# EEZ_tester_r1B2.net
KiCad netlist of a schematic drawn in EAGLE
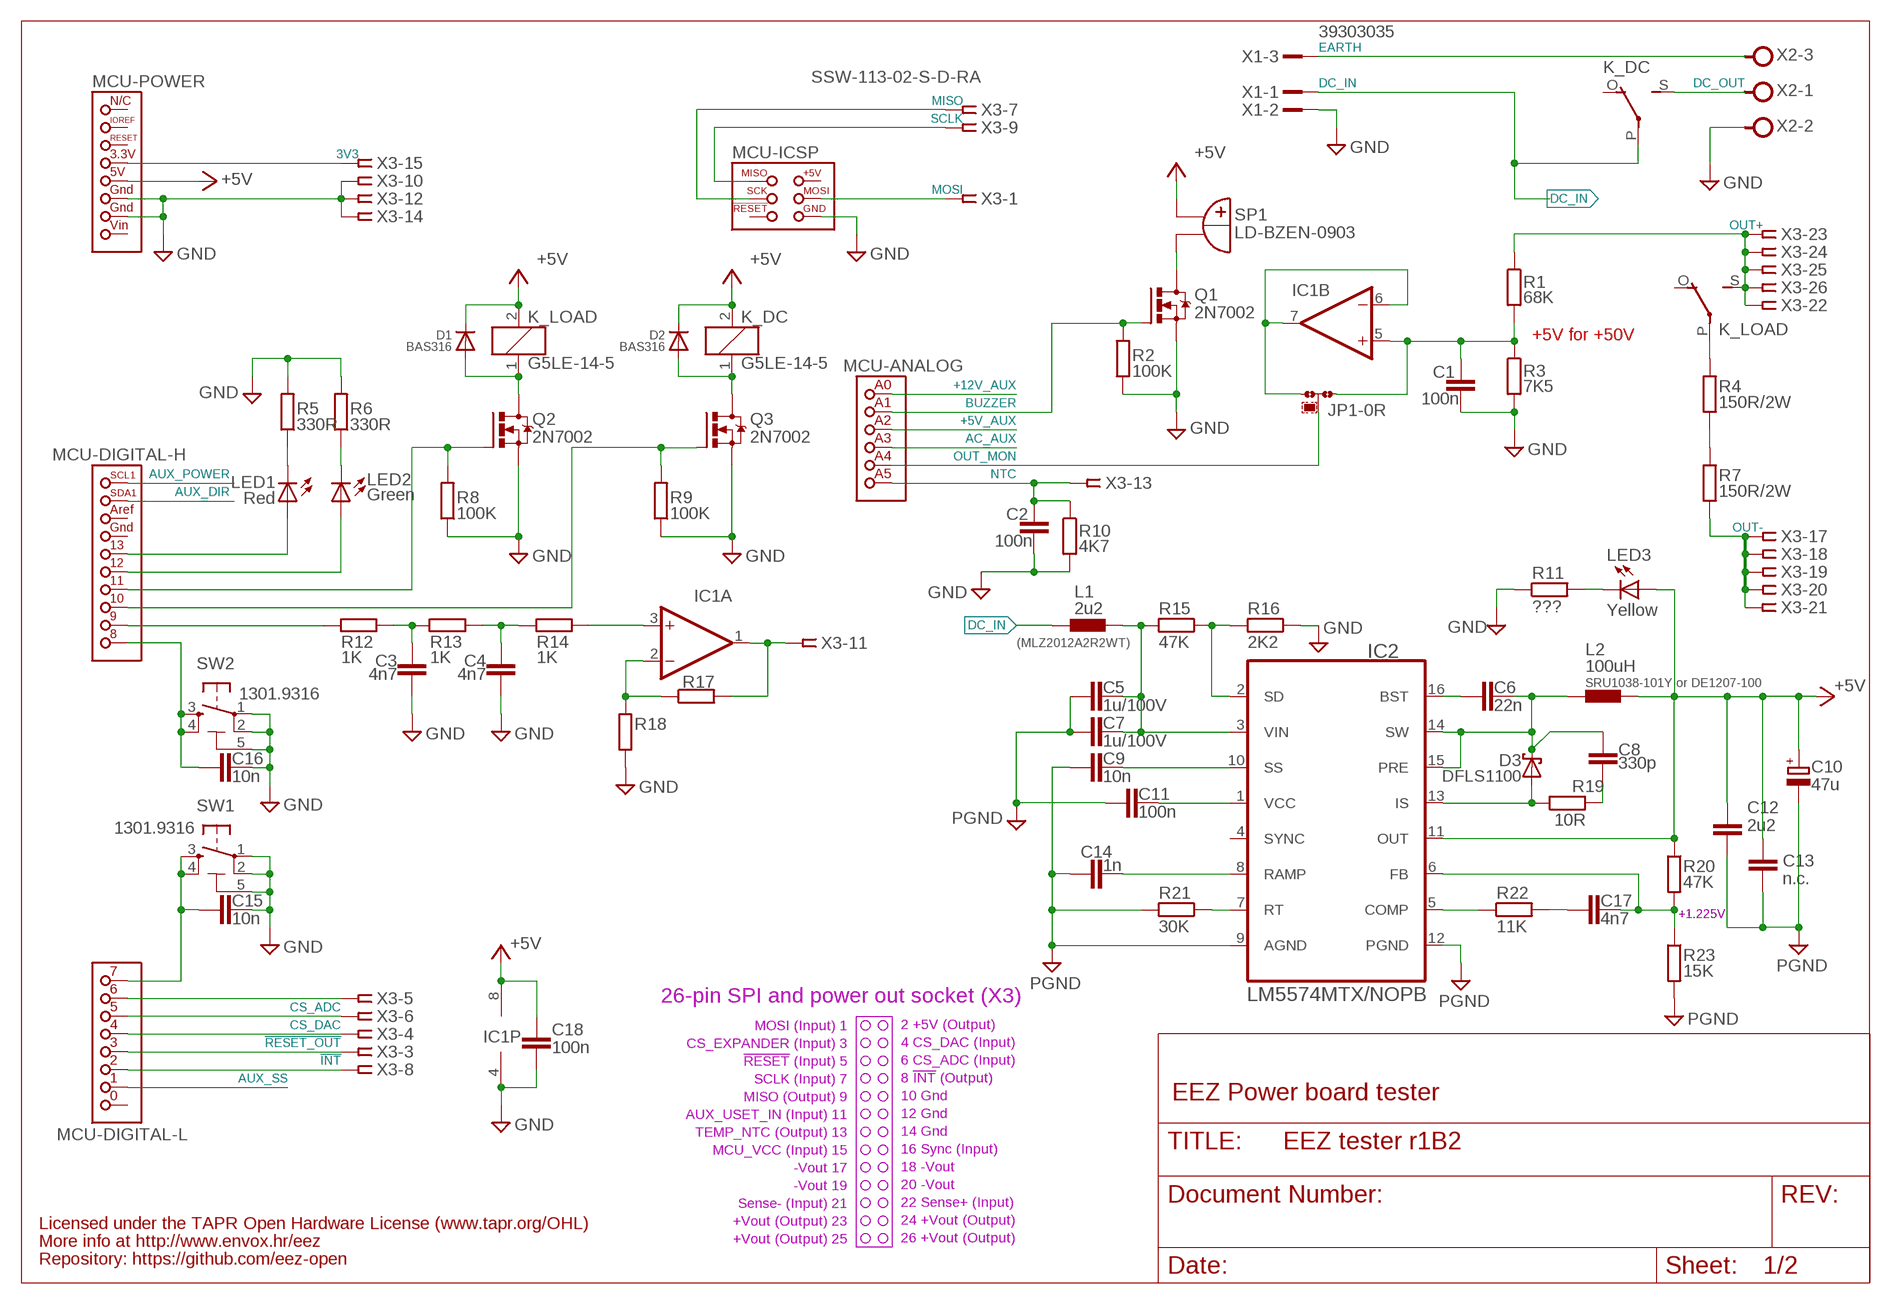
[diagram p0: schematic, sheet 1]
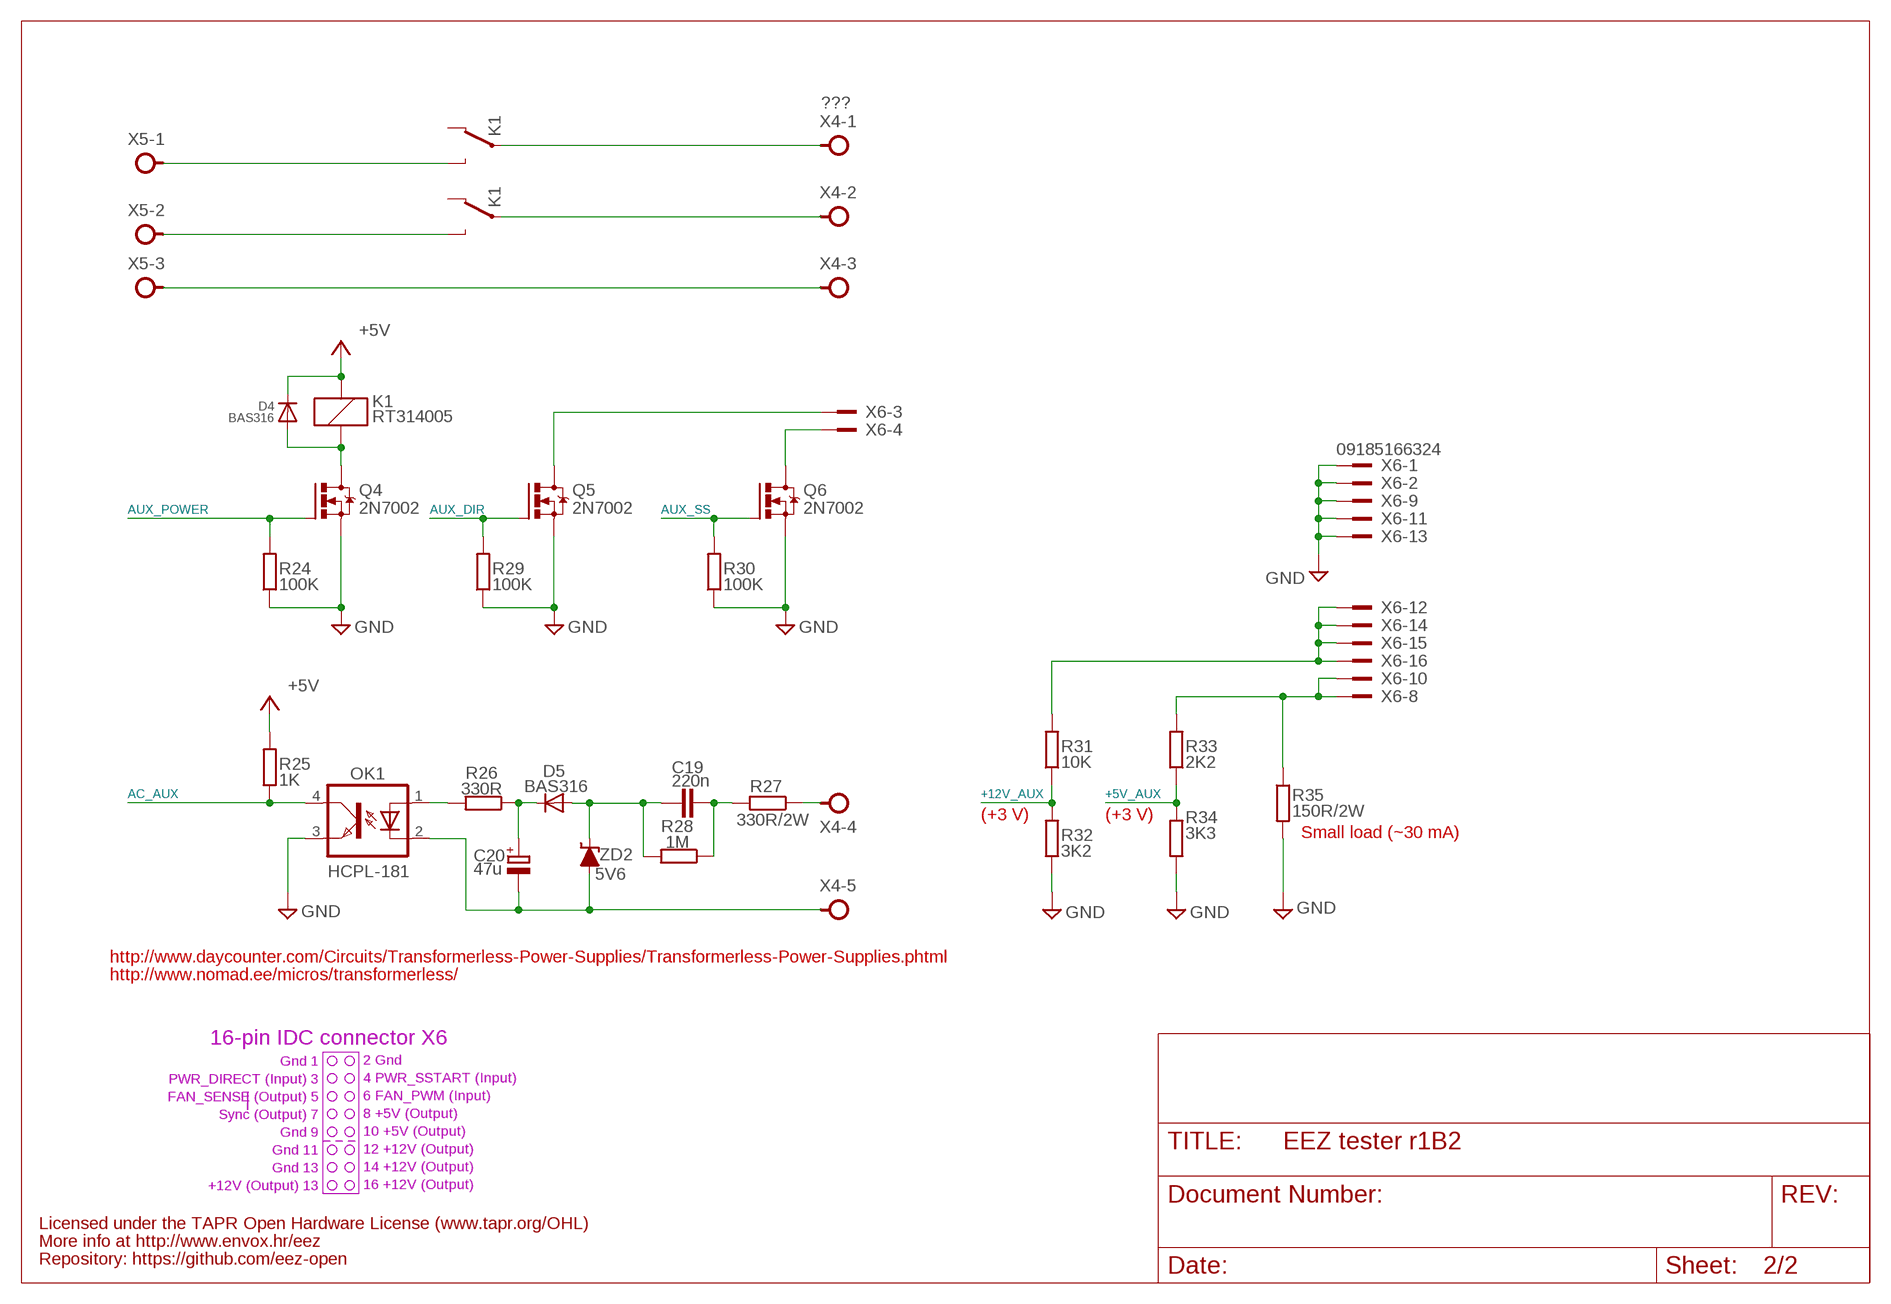
[diagram p1: schematic, sheet 2]

(export (version "E")
  (design (tool "Eeschema 10.0.6"))
  (components
    (comp (ref "C19")
      (value "220n")
      (footprint "eagle-import:C150-084X183")
      (libsource (lib "eagle-import") (part "C-EU150-084X183"))
    )
    (comp (ref "C20")
      (value "47u")
      (footprint "eagle-import:CAPAE660X610N")
      (libsource (lib "eagle-import") (part "ECAPPANASONIC_H"))
    )
    (comp (ref "D4")
      (value "BAS316")
      (footprint "eagle-import:SOD323-W")
      (libsource (lib "eagle-import") (part "DIODE-SOD323-W"))
    )
    (comp (ref "D5")
      (value "BAS316")
      (footprint "eagle-import:SOD323-W")
      (libsource (lib "eagle-import") (part "DIODE-SOD323-W"))
    )
    (comp (ref "K1")
      (value "RT314005")
      (footprint "eagle-import:RT-C_016A5_ROUND")
      (libsource (lib "eagle-import") (part "RELAY_RT314012-2"))
    )
    (comp (ref "OK1")
      (value "HCPL-181")
      (footprint "eagle-import:HCPL-181")
      (libsource (lib "eagle-import") (part "HCPL-181"))
    )
    (comp (ref "Q4")
      (value "2N7002")
      (footprint "eagle-import:SOT103P240X110-3N")
      (fields
        (field (name "MPN") "2N7002-7-F")
        (field (name "MPN_1") "2N7002-7-F")
        (field (name "OC_FARNELL") "1713823")
        (field (name "OC_NEWARK") "25R5679")
        (field (name "PACKAGE") "SOT-23-3")
        (field (name "SUPPLIER") "DIODES INC.")
      )
      (libsource (lib "eagle-import") (part "2N7002"))
    )
    (comp (ref "Q5")
      (value "2N7002")
      (footprint "eagle-import:SOT103P240X110-3N")
      (fields
        (field (name "MPN") "2N7002-7-F")
        (field (name "MPN_1") "2N7002-7-F")
        (field (name "OC_FARNELL") "1713823")
        (field (name "OC_NEWARK") "25R5679")
        (field (name "PACKAGE") "SOT-23-3")
        (field (name "SUPPLIER") "DIODES INC.")
      )
      (libsource (lib "eagle-import") (part "2N7002"))
    )
    (comp (ref "Q6")
      (value "2N7002")
      (footprint "eagle-import:SOT103P240X110-3N")
      (fields
        (field (name "MPN") "2N7002-7-F")
        (field (name "MPN_1") "2N7002-7-F")
        (field (name "OC_FARNELL") "1713823")
        (field (name "OC_NEWARK") "25R5679")
        (field (name "PACKAGE") "SOT-23-3")
        (field (name "SUPPLIER") "DIODES INC.")
      )
      (libsource (lib "eagle-import") (part "2N7002"))
    )
    (comp (ref "R24")
      (value "100K")
      (footprint "eagle-import:R0805")
      (libsource (lib "eagle-import") (part "R-EU_R0805"))
    )
    (comp (ref "R25")
      (value "1K")
      (footprint "eagle-import:R0805")
      (libsource (lib "eagle-import") (part "R-EU_R0805"))
    )
    (comp (ref "R26")
      (value "330R")
      (footprint "eagle-import:R0805")
      (libsource (lib "eagle-import") (part "R-EU_R0805"))
    )
    (comp (ref "R27")
      (value "330R/2W")
      (footprint "eagle-import:R2512")
      (libsource (lib "eagle-import") (part "R-EU_R2512"))
    )
    (comp (ref "R28")
      (value "1M")
      (footprint "eagle-import:R0805")
      (libsource (lib "eagle-import") (part "R-EU_R0805"))
    )
    (comp (ref "R29")
      (value "100K")
      (footprint "eagle-import:R0805")
      (libsource (lib "eagle-import") (part "R-EU_R0805"))
    )
    (comp (ref "R30")
      (value "100K")
      (footprint "eagle-import:R0805")
      (libsource (lib "eagle-import") (part "R-EU_R0805"))
    )
    (comp (ref "R31")
      (value "10K")
      (footprint "eagle-import:R0805")
      (libsource (lib "eagle-import") (part "R-EU_R0805"))
    )
    (comp (ref "R32")
      (value "3K2")
      (footprint "eagle-import:R0805")
      (libsource (lib "eagle-import") (part "R-EU_R0805"))
    )
    (comp (ref "R33")
      (value "2K2")
      (footprint "eagle-import:R0805")
      (libsource (lib "eagle-import") (part "R-EU_R0805"))
    )
    (comp (ref "R34")
      (value "3K3")
      (footprint "eagle-import:R0805")
      (libsource (lib "eagle-import") (part "R-EU_R0805"))
    )
    (comp (ref "R35")
      (value "150R/2W")
      (footprint "eagle-import:R2512")
      (libsource (lib "eagle-import") (part "R-EU_R2512"))
    )
    (comp (ref "X4")
      (value "???")
      (footprint "eagle-import:TBLOCK5.0_5")
      (libsource (lib "eagle-import") (part "TBLOCK5.0_5A"))
    )
    (comp (ref "X5")
      (value "TBLOCK5.0_3A")
      (footprint "eagle-import:TBLOCK5.0_3")
      (libsource (lib "eagle-import") (part "TBLOCK5.0_3A"))
    )
    (comp (ref "X6")
      (value "09185166324")
      (footprint "eagle-import:IDC-16PIN")
      (libsource (lib "eagle-import") (part "IDC-16PIN"))
    )
    (comp (ref "ZD2")
      (value "5V6")
      (footprint "eagle-import:SOD323-W")
      (libsource (lib "eagle-import") (part "ZENER-DIODESOD323"))
    )
    (comp (ref "C1")
      (value "100n")
      (footprint "eagle-import:C0603")
      (libsource (lib "eagle-import") (part "C-EUC0603"))
    )
    (comp (ref "C2")
      (value "100n")
      (footprint "eagle-import:C0603")
      (libsource (lib "eagle-import") (part "C-EUC0603"))
    )
    (comp (ref "C3")
      (value "4n7")
      (footprint "eagle-import:C0805")
      (libsource (lib "eagle-import") (part "C-EUC0805"))
    )
    (comp (ref "C4")
      (value "4n7")
      (footprint "eagle-import:C0805")
      (libsource (lib "eagle-import") (part "C-EUC0805"))
    )
    (comp (ref "C5")
      (value "1u/100V")
      (footprint "eagle-import:C1206")
      (libsource (lib "eagle-import") (part "C-EUC1206"))
    )
    (comp (ref "C6")
      (value "22n")
      (footprint "eagle-import:C0805")
      (libsource (lib "eagle-import") (part "C-EUC0805"))
    )
    (comp (ref "C7")
      (value "1u/100V")
      (footprint "eagle-import:C1206")
      (libsource (lib "eagle-import") (part "C-EUC1206"))
    )
    (comp (ref "C8")
      (value "330p")
      (footprint "eagle-import:C0805")
      (libsource (lib "eagle-import") (part "C-EUC0805"))
    )
    (comp (ref "C9")
      (value "10n")
      (footprint "eagle-import:C0805")
      (libsource (lib "eagle-import") (part "C-EUC0805"))
    )
    (comp (ref "C10")
      (value "47u")
      (footprint "eagle-import:CAPAE660X610N")
      (libsource (lib "eagle-import") (part "ECAPPANASONIC_H"))
    )
    (comp (ref "C11")
      (value "100n")
      (footprint "eagle-import:C0603")
      (libsource (lib "eagle-import") (part "C-EUC0603"))
    )
    (comp (ref "C12")
      (value "2u2")
      (footprint "eagle-import:C0805")
      (libsource (lib "eagle-import") (part "C-EUC0805"))
    )
    (comp (ref "C13")
      (value "n.c.")
      (footprint "eagle-import:C0805")
      (libsource (lib "eagle-import") (part "C-EUC0805"))
    )
    (comp (ref "C14")
      (value "1n")
      (footprint "eagle-import:C0805")
      (libsource (lib "eagle-import") (part "C-EUC0805"))
    )
    (comp (ref "C15")
      (value "10n")
      (footprint "eagle-import:C0805")
      (libsource (lib "eagle-import") (part "C-EUC0805"))
    )
    (comp (ref "C16")
      (value "10n")
      (footprint "eagle-import:C0805")
      (libsource (lib "eagle-import") (part "C-EUC0805"))
    )
    (comp (ref "C17")
      (value "4n7")
      (footprint "eagle-import:C0805")
      (libsource (lib "eagle-import") (part "C-EUC0805"))
    )
    (comp (ref "C18")
      (value "100n")
      (footprint "eagle-import:C0603")
      (libsource (lib "eagle-import") (part "C-EUC0603"))
    )
    (comp (ref "D1")
      (value "BAS316")
      (footprint "eagle-import:SOD323-W")
      (libsource (lib "eagle-import") (part "DIODE-SOD323-W"))
    )
    (comp (ref "D2")
      (value "BAS316")
      (footprint "eagle-import:SOD323-W")
      (libsource (lib "eagle-import") (part "DIODE-SOD323-W"))
    )
    (comp (ref "D3")
      (value "DFLS1100")
      (footprint "eagle-import:SOD123")
      (libsource (lib "eagle-import") (part "SCHOTTKYSOD123"))
    )
    (comp (ref "IC1")
      (value "TL072SOIC8")
      (footprint "eagle-import:SOIC127P600X173-8N")
      (libsource (lib "eagle-import") (part "TL072SOIC8"))
    )
    (comp (ref "IC2")
      (value "LM5574MTX/NOPB")
      (footprint "eagle-import:SOP65P640X110-16N")
      (fields (field (name "MPN") "LM5574MT"))
      (libsource (lib "eagle-import") (part "LM5574"))
    )
    (comp (ref "JP1")
      (value "0R-JUMPA")
      (footprint "eagle-import:A0R-JMP")
      (libsource (lib "eagle-import") (part "0R-JUMPA"))
    )
    (comp (ref "K_DC")
      (value "G5LE-14-5")
      (footprint "eagle-import:G5LE")
      (fields (field (name "OC_FARNELL") "unknown") (field (name "OC_NEWARK") "unknown"))
      (libsource (lib "eagle-import") (part "G5LE"))
    )
    (comp (ref "K_LOAD")
      (value "G5LE-14-5")
      (footprint "eagle-import:G5LE")
      (libsource (lib "eagle-import") (part "G5LE"))
    )
    (comp (ref "L1")
      (value "2u2")
      (footprint "eagle-import:0805")
      (libsource (lib "eagle-import") (part "L-EU0805"))
    )
    (comp (ref "L2")
      (value "100uH")
      (footprint "eagle-import:MSS1278")
      (libsource (lib "eagle-import") (part "COILCRAFT_MSS1278"))
    )
    (comp (ref "LED1")
      (value "Red")
      (footprint "eagle-import:LED3MM")
      (libsource (lib "eagle-import") (part "LED3MM"))
    )
    (comp (ref "LED2")
      (value "Green")
      (footprint "eagle-import:LED3MM")
      (libsource (lib "eagle-import") (part "LED3MM"))
    )
    (comp (ref "LED3")
      (value "Yellow")
      (footprint "eagle-import:LED3MM")
      (libsource (lib "eagle-import") (part "LED3MM"))
    )
    (comp (ref "MCU")
      (value "ARDUINO_LEONARDO")
      (footprint "eagle-import:ARDUINO_LEONARDO")
      (libsource (lib "eagle-import") (part "ARDUINO_LEONARDO"))
    )
    (comp (ref "Q1")
      (value "2N7002")
      (footprint "eagle-import:SOT103P240X110-3N")
      (fields (field (name "MPN") "2N7002-7-F"))
      (libsource (lib "eagle-import") (part "2N7002"))
    )
    (comp (ref "Q2")
      (value "2N7002")
      (footprint "eagle-import:SOT103P240X110-3N")
      (fields
        (field (name "MPN") "2N7002-7-F")
        (field (name "MPN_1") "2N7002-7-F")
        (field (name "OC_FARNELL") "1713823")
        (field (name "OC_NEWARK") "25R5679")
        (field (name "PACKAGE") "SOT-23-3")
        (field (name "SUPPLIER") "DIODES INC.")
      )
      (libsource (lib "eagle-import") (part "2N7002"))
    )
    (comp (ref "Q3")
      (value "2N7002")
      (footprint "eagle-import:SOT103P240X110-3N")
      (fields
        (field (name "MPN") "2N7002-7-F")
        (field (name "MPN_1") "2N7002-7-F")
        (field (name "OC_FARNELL") "1713823")
        (field (name "OC_NEWARK") "25R5679")
        (field (name "PACKAGE") "SOT-23-3")
        (field (name "SUPPLIER") "DIODES INC.")
      )
      (libsource (lib "eagle-import") (part "2N7002"))
    )
    (comp (ref "R1")
      (value "68K")
      (footprint "eagle-import:R0805")
      (libsource (lib "eagle-import") (part "R-EU_R0805"))
    )
    (comp (ref "R2")
      (value "100K")
      (footprint "eagle-import:R0805")
      (libsource (lib "eagle-import") (part "R-EU_R0805"))
    )
    (comp (ref "R3")
      (value "7K5")
      (footprint "eagle-import:R0805")
      (libsource (lib "eagle-import") (part "R-EU_R0805"))
    )
    (comp (ref "R4")
      (value "150R/2W")
      (footprint "eagle-import:0617_22")
      (libsource (lib "eagle-import") (part "R-EU_0617/22"))
    )
    (comp (ref "R5")
      (value "330R")
      (footprint "eagle-import:R0805")
      (libsource (lib "eagle-import") (part "R-EU_R0805"))
    )
    (comp (ref "R6")
      (value "330R")
      (footprint "eagle-import:R0805")
      (libsource (lib "eagle-import") (part "R-EU_R0805"))
    )
    (comp (ref "R7")
      (value "150R/2W")
      (footprint "eagle-import:0617_22")
      (libsource (lib "eagle-import") (part "R-EU_0617/22"))
    )
    (comp (ref "R8")
      (value "100K")
      (footprint "eagle-import:R0805")
      (libsource (lib "eagle-import") (part "R-EU_R0805"))
    )
    (comp (ref "R9")
      (value "100K")
      (footprint "eagle-import:R0805")
      (libsource (lib "eagle-import") (part "R-EU_R0805"))
    )
    (comp (ref "R10")
      (value "4K7")
      (footprint "eagle-import:R0805")
      (libsource (lib "eagle-import") (part "R-EU_R0805"))
    )
    (comp (ref "R11")
      (value "???")
      (footprint "eagle-import:R0805")
      (libsource (lib "eagle-import") (part "R-EU_R0805"))
    )
    (comp (ref "R12")
      (value "1K")
      (footprint "eagle-import:R0805")
      (libsource (lib "eagle-import") (part "R-EU_R0805"))
    )
    (comp (ref "R13")
      (value "1K")
      (footprint "eagle-import:R0805")
      (libsource (lib "eagle-import") (part "R-EU_R0805"))
    )
    (comp (ref "R14")
      (value "1K")
      (footprint "eagle-import:R0805")
      (libsource (lib "eagle-import") (part "R-EU_R0805"))
    )
    (comp (ref "R15")
      (value "47K")
      (footprint "eagle-import:R0805")
      (libsource (lib "eagle-import") (part "R-EU_R0805"))
    )
    (comp (ref "R16")
      (value "2K2")
      (footprint "eagle-import:R0805")
      (libsource (lib "eagle-import") (part "R-EU_R0805"))
    )
    (comp (ref "R17")
      (value "R-EU_R0805")
      (footprint "eagle-import:R0805")
      (libsource (lib "eagle-import") (part "R-EU_R0805"))
    )
    (comp (ref "R18")
      (value "R-EU_R0805")
      (footprint "eagle-import:R0805")
      (libsource (lib "eagle-import") (part "R-EU_R0805"))
    )
    (comp (ref "R19")
      (value "10R")
      (footprint "eagle-import:R1206")
      (libsource (lib "eagle-import") (part "R-EU_R1206"))
    )
    (comp (ref "R20")
      (value "47K")
      (footprint "eagle-import:R0805")
      (libsource (lib "eagle-import") (part "R-EU_R0805"))
    )
    (comp (ref "R21")
      (value "30K")
      (footprint "eagle-import:R0805")
      (libsource (lib "eagle-import") (part "R-EU_R0805"))
    )
    (comp (ref "R22")
      (value "11K")
      (footprint "eagle-import:R0805")
      (libsource (lib "eagle-import") (part "R-EU_R0805"))
    )
    (comp (ref "R23")
      (value "15K")
      (footprint "eagle-import:R0805")
      (libsource (lib "eagle-import") (part "R-EU_R0805"))
    )
    (comp (ref "SP1")
      (value "LD-BZEN-0903")
      (footprint "eagle-import:LD-BZEN-0903")
      (libsource (lib "eagle-import") (part "BUZZER-2"))
    )
    (comp (ref "SW1")
      (value "1301.9316")
      (footprint "eagle-import:TACTM-6XN")
      (libsource (lib "eagle-import") (part "TACT_SW"))
    )
    (comp (ref "SW2")
      (value "1301.9316")
      (footprint "eagle-import:TACTM-6XN")
      (libsource (lib "eagle-import") (part "TACT_SW"))
    )
    (comp (ref "X1")
      (value "39303035")
      (footprint "eagle-import:MINIFIT_6659-3")
      (libsource (lib "eagle-import") (part "MINIFIT-3PIN"))
    )
    (comp (ref "X2")
      (value "TBLOCK5.0_3A")
      (footprint "eagle-import:TBLOCK5.0_3")
      (libsource (lib "eagle-import") (part "TBLOCK5.0_3A"))
    )
    (comp (ref "X3")
      (value "SSW-113-02-S-D-RA")
      (footprint "eagle-import:TSW-113-02-S-D-RA")
      (libsource (lib "eagle-import") (part "SSW-113-02-S-D-RA"))
    )
  )
  (nets
    (net (code "1") (name "+5V") (class "Default")
      (node (ref "C10") (pin "1") (pinfunction "+_1") (pintype "passive"))
      (node (ref "C12") (pin "1") (pinfunction "1_1") (pintype "passive"))
      (node (ref "C13") (pin "1") (pinfunction "1_1") (pintype "passive"))
      (node (ref "C18") (pin "1") (pinfunction "1_1") (pintype "passive"))
      (node (ref "D1") (pin "C") (pinfunction "C_C") (pintype "passive"))
      (node (ref "D2") (pin "C") (pinfunction "C_C") (pintype "passive"))
      (node (ref "D4") (pin "C") (pinfunction "C_C") (pintype "passive"))
      (node (ref "IC1") (pin "8") (pinfunction "V+_8") (pintype "power_in"))
      (node (ref "IC2") (pin "11") (pinfunction "OUT_11") (pintype "output"))
      (node (ref "K1") (pin "A2") (pinfunction "C1_A2") (pintype "passive"))
      (node (ref "K_DC") (pin "2") (pinfunction "2_2") (pintype "passive"))
      (node (ref "K_LOAD") (pin "2") (pinfunction "2_2") (pintype "passive"))
      (node (ref "L2") (pin "2") (pinfunction "2_2") (pintype "passive"))
      (node (ref "LED3") (pin "A") (pinfunction "A_A") (pintype "passive"))
      (node (ref "MCU") (pin "5V") (pinfunction "5V_5V") (pintype "bidirectional"))
      (node (ref "R20") (pin "1") (pinfunction "1_1") (pintype "passive"))
      (node (ref "R25") (pin "2") (pinfunction "2_2") (pintype "passive"))
      (node (ref "SP1") (pin "+B") (pinfunction "+_+B") (pintype "passive"))
    )
    (net (code "2") (name "+5V_AUX") (class "Default")
      (node (ref "MCU") (pin "A2") (pinfunction "ADC2_A2") (pintype "bidirectional"))
      (node (ref "R33") (pin "1") (pinfunction "1_1") (pintype "passive"))
      (node (ref "R34") (pin "2") (pinfunction "2_2") (pintype "passive"))
    )
    (net (code "3") (name "+12V_AUX") (class "Default")
      (node (ref "MCU") (pin "A0") (pinfunction "ADC0_A0") (pintype "bidirectional"))
      (node (ref "R31") (pin "1") (pinfunction "1_1") (pintype "passive"))
      (node (ref "R32") (pin "2") (pinfunction "2_2") (pintype "passive"))
    )
    (net (code "4") (name "3V3") (class "Default")
      (node (ref "MCU") (pin "3.3V") (pinfunction "3V3_3.3V") (pintype "bidirectional"))
      (node (ref "X3") (pin "15") (pinfunction "1_15") (pintype "passive"))
    )
    (net (code "5") (name "AC_AUX") (class "Default")
      (node (ref "MCU") (pin "A3") (pinfunction "ADC3_A3") (pintype "bidirectional"))
      (node (ref "OK1") (pin "4") (pinfunction "COL_4") (pintype "passive"))
      (node (ref "R25") (pin "1") (pinfunction "1_1") (pintype "passive"))
    )
    (net (code "6") (name "AUX_DIR") (class "Default")
      (node (ref "MCU") (pin "SDA1") (pinfunction "SDA1_SDA1") (pintype "bidirectional"))
      (node (ref "Q5") (pin "1") (pinfunction "G_1") (pintype "passive"))
      (node (ref "R29") (pin "2") (pinfunction "2_2") (pintype "passive"))
    )
    (net (code "7") (name "AUX_POWER") (class "Default")
      (node (ref "MCU") (pin "SCL1") (pinfunction "SCL1_SCL1") (pintype "bidirectional"))
      (node (ref "Q4") (pin "1") (pinfunction "G_1") (pintype "passive"))
      (node (ref "R24") (pin "2") (pinfunction "2_2") (pintype "passive"))
    )
    (net (code "8") (name "AUX_SS") (class "Default")
      (node (ref "MCU") (pin "1") (pinfunction "1(PE1)_1") (pintype "bidirectional"))
      (node (ref "Q6") (pin "1") (pinfunction "G_1") (pintype "passive"))
      (node (ref "R30") (pin "2") (pinfunction "2_2") (pintype "passive"))
    )
    (net (code "9") (name "BUZZER") (class "Default")
      (node (ref "MCU") (pin "A1") (pinfunction "ADC1_A1") (pintype "bidirectional"))
      (node (ref "Q1") (pin "1") (pinfunction "G_1") (pintype "passive"))
      (node (ref "R2") (pin "2") (pinfunction "2_2") (pintype "passive"))
    )
    (net (code "10") (name "CS_ADC") (class "Default")
      (node (ref "MCU") (pin "5") (pinfunction "5(PE3)_5") (pintype "bidirectional"))
      (node (ref "X3") (pin "6") (pinfunction "1_6") (pintype "passive"))
    )
    (net (code "11") (name "CS_DAC") (class "Default")
      (node (ref "MCU") (pin "4") (pinfunction "4(PG5)_4") (pintype "bidirectional"))
      (node (ref "X3") (pin "4") (pinfunction "1_4") (pintype "passive"))
    )
    (net (code "12") (name "DC_IN") (class "Default")
      (node (ref "K_DC") (pin "P") (pinfunction "P_P") (pintype "passive"))
      (node (ref "L1") (pin "1") (pinfunction "1_1") (pintype "passive"))
      (node (ref "X1") (pin "1") (pinfunction "1_1") (pintype "passive"))
    )
    (net (code "13") (name "DC_OUT") (class "Default")
      (node (ref "K_DC") (pin "S") (pinfunction "S_S") (pintype "passive"))
      (node (ref "X2") (pin "1") (pinfunction "1_1") (pintype "bidirectional"))
    )
    (net (code "14") (name "EARTH") (class "Default")
      (node (ref "X1") (pin "3") (pinfunction "1_3") (pintype "passive"))
      (node (ref "X2") (pin "3") (pinfunction "1_3") (pintype "bidirectional"))
    )
    (net (code "15") (name "GND") (class "Default")
      (node (ref "C1") (pin "1") (pinfunction "1_1") (pintype "passive"))
      (node (ref "C10") (pin "2") (pinfunction "-_2") (pintype "passive"))
      (node (ref "C11") (pin "1") (pinfunction "1_1") (pintype "passive"))
      (node (ref "C12") (pin "2") (pinfunction "2_2") (pintype "passive"))
      (node (ref "C13") (pin "2") (pinfunction "2_2") (pintype "passive"))
      (node (ref "C14") (pin "1") (pinfunction "1_1") (pintype "passive"))
      (node (ref "C15") (pin "2") (pinfunction "2_2") (pintype "passive"))
      (node (ref "C16") (pin "2") (pinfunction "2_2") (pintype "passive"))
      (node (ref "C18") (pin "2") (pinfunction "2_2") (pintype "passive"))
      (node (ref "C2") (pin "1") (pinfunction "1_1") (pintype "passive"))
      (node (ref "C3") (pin "2") (pinfunction "2_2") (pintype "passive"))
      (node (ref "C4") (pin "2") (pinfunction "2_2") (pintype "passive"))
      (node (ref "C5") (pin "2") (pinfunction "2_2") (pintype "passive"))
      (node (ref "C7") (pin "2") (pinfunction "2_2") (pintype "passive"))
      (node (ref "C9") (pin "2") (pinfunction "2_2") (pintype "passive"))
      (node (ref "IC1") (pin "4") (pinfunction "V-_4") (pintype "power_in"))
      (node (ref "IC2") (pin "12") (pinfunction "PGND_12") (pintype "passive"))
      (node (ref "IC2") (pin "9") (pinfunction "AGND_9") (pintype "passive"))
      (node (ref "MCU") (pin "GND1") (pinfunction "GND1_GND1") (pintype "bidirectional"))
      (node (ref "MCU") (pin "GND2") (pinfunction "GND2_GND2") (pintype "bidirectional"))
      (node (ref "MCU") (pin "ICSP_GND") (pinfunction "GND_ICSP_GND") (pintype "bidirectional"))
      (node (ref "OK1") (pin "3") (pinfunction "EMIT_3") (pintype "passive"))
      (node (ref "Q1") (pin "2") (pinfunction "S_2") (pintype "passive"))
      (node (ref "Q2") (pin "2") (pinfunction "S_2") (pintype "passive"))
      (node (ref "Q3") (pin "2") (pinfunction "S_2") (pintype "passive"))
      (node (ref "Q4") (pin "2") (pinfunction "S_2") (pintype "passive"))
      (node (ref "Q5") (pin "2") (pinfunction "S_2") (pintype "passive"))
      (node (ref "Q6") (pin "2") (pinfunction "S_2") (pintype "passive"))
      (node (ref "R10") (pin "2") (pinfunction "2_2") (pintype "passive"))
      (node (ref "R11") (pin "1") (pinfunction "1_1") (pintype "passive"))
      (node (ref "R16") (pin "1") (pinfunction "1_1") (pintype "passive"))
      (node (ref "R18") (pin "2") (pinfunction "2_2") (pintype "passive"))
      (node (ref "R2") (pin "1") (pinfunction "1_1") (pintype "passive"))
      (node (ref "R21") (pin "2") (pinfunction "2_2") (pintype "passive"))
      (node (ref "R23") (pin "2") (pinfunction "2_2") (pintype "passive"))
      (node (ref "R24") (pin "1") (pinfunction "1_1") (pintype "passive"))
      (node (ref "R29") (pin "1") (pinfunction "1_1") (pintype "passive"))
      (node (ref "R3") (pin "2") (pinfunction "2_2") (pintype "passive"))
      (node (ref "R30") (pin "1") (pinfunction "1_1") (pintype "passive"))
      (node (ref "R32") (pin "1") (pinfunction "1_1") (pintype "passive"))
      (node (ref "R34") (pin "1") (pinfunction "1_1") (pintype "passive"))
      (node (ref "R35") (pin "2") (pinfunction "2_2") (pintype "passive"))
      (node (ref "R5") (pin "2") (pinfunction "2_2") (pintype "passive"))
      (node (ref "R6") (pin "2") (pinfunction "2_2") (pintype "passive"))
      (node (ref "R8") (pin "1") (pinfunction "1_1") (pintype "passive"))
      (node (ref "R9") (pin "1") (pinfunction "1_1") (pintype "passive"))
      (node (ref "SW1") (pin "1") (pinfunction "1_1") (pintype "passive"))
      (node (ref "SW1") (pin "2") (pinfunction "2_2") (pintype "passive"))
      (node (ref "SW1") (pin "5") (pinfunction "5-GND_5") (pintype "passive"))
      (node (ref "SW2") (pin "1") (pinfunction "1_1") (pintype "passive"))
      (node (ref "SW2") (pin "2") (pinfunction "2_2") (pintype "passive"))
      (node (ref "SW2") (pin "5") (pinfunction "5-GND_5") (pintype "passive"))
      (node (ref "X1") (pin "2") (pinfunction "1_2") (pintype "passive"))
      (node (ref "X2") (pin "2") (pinfunction "1_2") (pintype "bidirectional"))
      (node (ref "X3") (pin "10") (pinfunction "1_10") (pintype "passive"))
      (node (ref "X3") (pin "12") (pinfunction "1_12") (pintype "passive"))
      (node (ref "X3") (pin "14") (pinfunction "1_14") (pintype "passive"))
      (node (ref "X6") (pin "1") (pinfunction "1_1") (pintype "passive"))
      (node (ref "X6") (pin "11") (pinfunction "1_11") (pintype "passive"))
      (node (ref "X6") (pin "13") (pinfunction "1_13") (pintype "passive"))
      (node (ref "X6") (pin "2") (pinfunction "1_2") (pintype "passive"))
      (node (ref "X6") (pin "9") (pinfunction "1_9") (pintype "passive"))
    )
    (net (code "16") (name "MISO") (class "Default")
      (node (ref "MCU") (pin "ICSP_SCK") (pinfunction "SCK_ICSP_SCK") (pintype "bidirectional"))
      (node (ref "X3") (pin "7") (pinfunction "1_7") (pintype "passive"))
    )
    (net (code "17") (name "MOSI") (class "Default")
      (node (ref "MCU") (pin "ICSP_MOSI") (pinfunction "MOSI_ICSP_MOSI") (pintype "bidirectional"))
      (node (ref "X3") (pin "1") (pinfunction "1_1") (pintype "passive"))
    )
    (net (code "18") (name "NTC") (class "Default")
      (node (ref "C2") (pin "2") (pinfunction "2_2") (pintype "passive"))
      (node (ref "MCU") (pin "A5") (pinfunction "ADC5_A5") (pintype "bidirectional"))
      (node (ref "R10") (pin "1") (pinfunction "1_1") (pintype "passive"))
      (node (ref "X3") (pin "13") (pinfunction "1_13") (pintype "passive"))
    )
    (net (code "19") (name "Net-(C3-Pad1)") (class "Default")
      (node (ref "C3") (pin "1") (pinfunction "1_1") (pintype "passive"))
      (node (ref "R12") (pin "1") (pinfunction "1_1") (pintype "passive"))
      (node (ref "R13") (pin "2") (pinfunction "2_2") (pintype "passive"))
    )
    (net (code "20") (name "Net-(C4-Pad1)") (class "Default")
      (node (ref "C4") (pin "1") (pinfunction "1_1") (pintype "passive"))
      (node (ref "R13") (pin "1") (pinfunction "1_1") (pintype "passive"))
      (node (ref "R14") (pin "2") (pinfunction "2_2") (pintype "passive"))
    )
    (net (code "21") (name "Net-(C8-Pad2)") (class "Default")
      (node (ref "C8") (pin "2") (pinfunction "2_2") (pintype "passive"))
      (node (ref "R19") (pin "2") (pinfunction "2_2") (pintype "passive"))
    )
    (net (code "22") (name "Net-(C17-Pad2)") (class "Default")
      (node (ref "C17") (pin "2") (pinfunction "2_2") (pintype "passive"))
      (node (ref "R22") (pin "2") (pinfunction "2_2") (pintype "passive"))
    )
    (net (code "23") (name "Net-(C19-Pad1)") (class "Default")
      (node (ref "C19") (pin "1") (pinfunction "1_1") (pintype "passive"))
      (node (ref "D5") (pin "A") (pinfunction "A_A") (pintype "passive"))
      (node (ref "R28") (pin "2") (pinfunction "2_2") (pintype "passive"))
      (node (ref "ZD2") (pin "C") (pinfunction "C_C") (pintype "passive"))
    )
    (net (code "24") (name "Net-(C19-Pad2)") (class "Default")
      (node (ref "C19") (pin "2") (pinfunction "2_2") (pintype "passive"))
      (node (ref "R27") (pin "2") (pinfunction "2_2") (pintype "passive"))
      (node (ref "R28") (pin "1") (pinfunction "1_1") (pintype "passive"))
    )
    (net (code "25") (name "Net-(C20-+)") (class "Default")
      (node (ref "C20") (pin "1") (pinfunction "+_1") (pintype "passive"))
      (node (ref "D5") (pin "C") (pinfunction "C_C") (pintype "passive"))
      (node (ref "R26") (pin "1") (pinfunction "1_1") (pintype "passive"))
    )
    (net (code "26") (name "Net-(C20--)") (class "Default")
      (node (ref "C20") (pin "2") (pinfunction "-_2") (pintype "passive"))
      (node (ref "OK1") (pin "2") (pinfunction "C_2") (pintype "passive"))
      (node (ref "X4") (pin "5") (pinfunction "1_5") (pintype "bidirectional"))
      (node (ref "ZD2") (pin "A") (pinfunction "A_A") (pintype "passive"))
    )
    (net (code "27") (name "Net-(IC1A-+IN)") (class "Default")
      (node (ref "IC1") (pin "3") (pinfunction "+IN_3") (pintype "input"))
      (node (ref "R14") (pin "1") (pinfunction "1_1") (pintype "passive"))
    )
    (net (code "28") (name "Net-(IC1A--IN)") (class "Default")
      (node (ref "IC1") (pin "2") (pinfunction "-IN_2") (pintype "input"))
      (node (ref "R17") (pin "1") (pinfunction "1_1") (pintype "passive"))
      (node (ref "R18") (pin "1") (pinfunction "1_1") (pintype "passive"))
    )
    (net (code "29") (name "Net-(IC1A-OUT)") (class "Default")
      (node (ref "IC1") (pin "1") (pinfunction "OUT_1") (pintype "output"))
      (node (ref "R17") (pin "2") (pinfunction "2_2") (pintype "passive"))
      (node (ref "X3") (pin "11") (pinfunction "1_11") (pintype "passive"))
    )
    (net (code "30") (name "Net-(IC1B-+IN)") (class "Default")
      (node (ref "C1") (pin "2") (pinfunction "2_2") (pintype "passive"))
      (node (ref "IC1") (pin "5") (pinfunction "+IN_5") (pintype "input"))
      (node (ref "JP1") (pin "1") (pinfunction "1_1") (pintype "passive"))
      (node (ref "R1") (pin "2") (pinfunction "2_2") (pintype "passive"))
      (node (ref "R3") (pin "1") (pinfunction "1_1") (pintype "passive"))
    )
    (net (code "31") (name "Net-(IC1B--IN)") (class "Default")
      (node (ref "IC1") (pin "6") (pinfunction "-IN_6") (pintype "input"))
      (node (ref "IC1") (pin "7") (pinfunction "OUT_7") (pintype "output"))
      (node (ref "JP1") (pin "3") (pinfunction "3_3") (pintype "passive"))
    )
    (net (code "32") (name "Net-(IC2-BST)") (class "Default")
      (node (ref "C6") (pin "2") (pinfunction "2_2") (pintype "passive"))
      (node (ref "IC2") (pin "16") (pinfunction "BST_16") (pintype "input"))
    )
    (net (code "33") (name "Net-(IC2-COMP)") (class "Default")
      (node (ref "IC2") (pin "5") (pinfunction "COMP_5") (pintype "input"))
      (node (ref "R22") (pin "1") (pinfunction "1_1") (pintype "passive"))
    )
    (net (code "34") (name "Net-(IC2-FB)") (class "Default")
      (node (ref "C17") (pin "1") (pinfunction "1_1") (pintype "passive"))
      (node (ref "IC2") (pin "6") (pinfunction "FB_6") (pintype "input"))
      (node (ref "R20") (pin "2") (pinfunction "2_2") (pintype "passive"))
      (node (ref "R23") (pin "1") (pinfunction "1_1") (pintype "passive"))
    )
    (net (code "35") (name "Net-(IC2-IS)") (class "Default")
      (node (ref "D3") (pin "A") (pinfunction "A_A") (pintype "passive"))
      (node (ref "IC2") (pin "13") (pinfunction "IS_13") (pintype "input"))
      (node (ref "R19") (pin "1") (pinfunction "1_1") (pintype "passive"))
    )
    (net (code "36") (name "Net-(IC2-PRE)") (class "Default")
      (node (ref "C6") (pin "1") (pinfunction "1_1") (pintype "passive"))
      (node (ref "C8") (pin "1") (pinfunction "1_1") (pintype "passive"))
      (node (ref "D3") (pin "C") (pinfunction "C_C") (pintype "passive"))
      (node (ref "IC2") (pin "14") (pinfunction "SW_14") (pintype "output"))
      (node (ref "IC2") (pin "15") (pinfunction "PRE_15") (pintype "input"))
      (node (ref "L2") (pin "1") (pinfunction "1_1") (pintype "passive"))
    )
    (net (code "37") (name "Net-(IC2-RAMP)") (class "Default")
      (node (ref "C14") (pin "2") (pinfunction "2_2") (pintype "passive"))
      (node (ref "IC2") (pin "8") (pinfunction "RAMP_8") (pintype "input"))
    )
    (net (code "38") (name "Net-(IC2-RT)") (class "Default")
      (node (ref "IC2") (pin "7") (pinfunction "RT_7") (pintype "input"))
      (node (ref "R21") (pin "1") (pinfunction "1_1") (pintype "passive"))
    )
    (net (code "39") (name "Net-(IC2-SD)") (class "Default")
      (node (ref "IC2") (pin "2") (pinfunction "SD_2") (pintype "input"))
      (node (ref "R15") (pin "1") (pinfunction "1_1") (pintype "passive"))
      (node (ref "R16") (pin "2") (pinfunction "2_2") (pintype "passive"))
    )
    (net (code "40") (name "Net-(IC2-SS)") (class "Default")
      (node (ref "C9") (pin "1") (pinfunction "1_1") (pintype "passive"))
      (node (ref "IC2") (pin "10") (pinfunction "SS_10") (pintype "input"))
    )
    (net (code "41") (name "Net-(IC2-VCC)") (class "Default")
      (node (ref "C11") (pin "2") (pinfunction "2_2") (pintype "passive"))
      (node (ref "IC2") (pin "1") (pinfunction "VCC_1") (pintype "power_in"))
    )
    (net (code "42") (name "Net-(IC2-VIN)") (class "Default")
      (node (ref "C5") (pin "1") (pinfunction "1_1") (pintype "passive"))
      (node (ref "C7") (pin "1") (pinfunction "1_1") (pintype "passive"))
      (node (ref "IC2") (pin "3") (pinfunction "VIN_3") (pintype "input"))
      (node (ref "L1") (pin "2") (pinfunction "2_2") (pintype "passive"))
      (node (ref "R15") (pin "2") (pinfunction "2_2") (pintype "passive"))
    )
    (net (code "43") (name "Net-(K1A-O)") (class "Default")
      (node (ref "K1") (pin "14A") (pinfunction "O_14A") (pintype "passive"))
      (node (ref "X5") (pin "2") (pinfunction "1_2") (pintype "bidirectional"))
    )
    (net (code "44") (name "Net-(K1A-P)") (class "Default")
      (node (ref "K1") (pin "11A") (pinfunction "P_11A") (pintype "passive"))
      (node (ref "X4") (pin "2") (pinfunction "1_2") (pintype "bidirectional"))
    )
    (net (code "45") (name "Net-(K1B-O)") (class "Default")
      (node (ref "K1") (pin "14B") (pinfunction "O_14B") (pintype "passive"))
      (node (ref "X5") (pin "1") (pinfunction "1_1") (pintype "bidirectional"))
    )
    (net (code "46") (name "Net-(K1B-P)") (class "Default")
      (node (ref "K1") (pin "11B") (pinfunction "P_11B") (pintype "passive"))
      (node (ref "X4") (pin "1") (pinfunction "1_1") (pintype "bidirectional"))
    )
    (net (code "47") (name "Net-(K1C-C2)") (class "Default")
      (node (ref "D4") (pin "A") (pinfunction "A_A") (pintype "passive"))
      (node (ref "K1") (pin "A1") (pinfunction "C2_A1") (pintype "passive"))
      (node (ref "Q4") (pin "3") (pinfunction "D_3") (pintype "passive"))
    )
    (net (code "48") (name "Net-(K_LOAD-PadP)") (class "Default")
      (node (ref "K_LOAD") (pin "P") (pinfunction "P_P") (pintype "passive"))
      (node (ref "R4") (pin "2") (pinfunction "2_2") (pintype "passive"))
    )
    (net (code "49") (name "Net-(LED1-C)") (class "Default")
      (node (ref "LED1") (pin "K") (pinfunction "C_K") (pintype "passive"))
      (node (ref "R5") (pin "1") (pinfunction "1_1") (pintype "passive"))
    )
    (net (code "50") (name "Net-(LED1-PadA)") (class "Default")
      (node (ref "LED1") (pin "A") (pinfunction "A_A") (pintype "passive"))
      (node (ref "MCU") (pin "13") (pinfunction "13_13") (pintype "bidirectional"))
    )
    (net (code "51") (name "Net-(LED2-C)") (class "Default")
      (node (ref "LED2") (pin "K") (pinfunction "C_K") (pintype "passive"))
      (node (ref "R6") (pin "1") (pinfunction "1_1") (pintype "passive"))
    )
    (net (code "52") (name "Net-(LED2-PadA)") (class "Default")
      (node (ref "LED2") (pin "A") (pinfunction "A_A") (pintype "passive"))
      (node (ref "MCU") (pin "12") (pinfunction "12_12") (pintype "bidirectional"))
    )
    (net (code "53") (name "Net-(LED3-C)") (class "Default")
      (node (ref "LED3") (pin "K") (pinfunction "C_K") (pintype "passive"))
      (node (ref "R11") (pin "2") (pinfunction "2_2") (pintype "passive"))
    )
    (net (code "54") (name "Net-(MCUB-8(PH5))") (class "Default")
      (node (ref "C16") (pin "1") (pinfunction "1_1") (pintype "passive"))
      (node (ref "MCU") (pin "8") (pinfunction "8(PH5)_8") (pintype "bidirectional"))
      (node (ref "SW2") (pin "3") (pinfunction "3_3") (pintype "passive"))
      (node (ref "SW2") (pin "4") (pinfunction "4_4") (pintype "passive"))
    )
    (net (code "55") (name "Net-(MCUB-9(PH6))") (class "Default")
      (node (ref "MCU") (pin "9") (pinfunction "9(PH6)_9") (pintype "bidirectional"))
      (node (ref "R12") (pin "2") (pinfunction "2_2") (pintype "passive"))
    )
    (net (code "56") (name "Net-(MCUC-6(PH3))") (class "Default")
      (node (ref "MCU") (pin "6") (pinfunction "6(PH3)_6") (pintype "bidirectional"))
      (node (ref "X3") (pin "5") (pinfunction "1_5") (pintype "passive"))
    )
    (net (code "57") (name "Net-(MCUC-7(PH4))") (class "Default")
      (node (ref "C15") (pin "1") (pinfunction "1_1") (pintype "passive"))
      (node (ref "MCU") (pin "7") (pinfunction "7(PH4)_7") (pintype "bidirectional"))
      (node (ref "SW1") (pin "3") (pinfunction "3_3") (pintype "passive"))
      (node (ref "SW1") (pin "4") (pinfunction "4_4") (pintype "passive"))
    )
    (net (code "58") (name "Net-(OK1-A)") (class "Default")
      (node (ref "OK1") (pin "1") (pinfunction "A_1") (pintype "passive"))
      (node (ref "R26") (pin "2") (pinfunction "2_2") (pintype "passive"))
    )
    (net (code "59") (name "Net-(Q1-D)") (class "Default")
      (node (ref "Q1") (pin "3") (pinfunction "D_3") (pintype "passive"))
      (node (ref "SP1") (pin "-B") (pinfunction "-_-B") (pintype "passive"))
    )
    (net (code "60") (name "Net-(Q2-D)") (class "Default")
      (node (ref "D1") (pin "A") (pinfunction "A_A") (pintype "passive"))
      (node (ref "K_LOAD") (pin "1") (pinfunction "1_1") (pintype "passive"))
      (node (ref "Q2") (pin "3") (pinfunction "D_3") (pintype "passive"))
    )
    (net (code "61") (name "Net-(Q2-G)") (class "Default")
      (node (ref "MCU") (pin "11") (pinfunction "11_11") (pintype "bidirectional"))
      (node (ref "Q2") (pin "1") (pinfunction "G_1") (pintype "passive"))
      (node (ref "R8") (pin "2") (pinfunction "2_2") (pintype "passive"))
    )
    (net (code "62") (name "Net-(Q3-D)") (class "Default")
      (node (ref "D2") (pin "A") (pinfunction "A_A") (pintype "passive"))
      (node (ref "K_DC") (pin "1") (pinfunction "1_1") (pintype "passive"))
      (node (ref "Q3") (pin "3") (pinfunction "D_3") (pintype "passive"))
    )
    (net (code "63") (name "Net-(Q3-G)") (class "Default")
      (node (ref "MCU") (pin "10") (pinfunction "10_10") (pintype "bidirectional"))
      (node (ref "Q3") (pin "1") (pinfunction "G_1") (pintype "passive"))
      (node (ref "R9") (pin "2") (pinfunction "2_2") (pintype "passive"))
    )
    (net (code "64") (name "Net-(Q5-D)") (class "Default")
      (node (ref "Q5") (pin "3") (pinfunction "D_3") (pintype "passive"))
      (node (ref "X6") (pin "3") (pinfunction "1_3") (pintype "passive"))
    )
    (net (code "65") (name "Net-(Q6-D)") (class "Default")
      (node (ref "Q6") (pin "3") (pinfunction "D_3") (pintype "passive"))
      (node (ref "X6") (pin "4") (pinfunction "1_4") (pintype "passive"))
    )
    (net (code "66") (name "Net-(R4-Pad1)") (class "Default")
      (node (ref "R4") (pin "1") (pinfunction "1_1") (pintype "passive"))
      (node (ref "R7") (pin "2") (pinfunction "2_2") (pintype "passive"))
    )
    (net (code "67") (name "Net-(X4C-1)") (class "Default")
      (node (ref "X4") (pin "3") (pinfunction "1_3") (pintype "bidirectional"))
      (node (ref "X5") (pin "3") (pinfunction "1_3") (pintype "bidirectional"))
    )
    (net (code "68") (name "Net-(X4D-1)") (class "Default")
      (node (ref "R27") (pin "1") (pinfunction "1_1") (pintype "passive"))
      (node (ref "X4") (pin "4") (pinfunction "1_4") (pintype "bidirectional"))
    )
    (net (code "69") (name "Net-(X6B-1)") (class "Default")
      (node (ref "R33") (pin "2") (pinfunction "2_2") (pintype "passive"))
      (node (ref "R35") (pin "1") (pinfunction "1_1") (pintype "passive"))
      (node (ref "X6") (pin "10") (pinfunction "1_10") (pintype "passive"))
      (node (ref "X6") (pin "8") (pinfunction "1_8") (pintype "passive"))
    )
    (net (code "70") (name "Net-(X6D-1)") (class "Default")
      (node (ref "R31") (pin "2") (pinfunction "2_2") (pintype "passive"))
      (node (ref "X6") (pin "12") (pinfunction "1_12") (pintype "passive"))
      (node (ref "X6") (pin "14") (pinfunction "1_14") (pintype "passive"))
      (node (ref "X6") (pin "15") (pinfunction "1_15") (pintype "passive"))
      (node (ref "X6") (pin "16") (pinfunction "1_16") (pintype "passive"))
    )
    (net (code "71") (name "OUT+") (class "Default")
      (node (ref "K_LOAD") (pin "S") (pinfunction "S_S") (pintype "passive"))
      (node (ref "R1") (pin "1") (pinfunction "1_1") (pintype "passive"))
      (node (ref "X3") (pin "22") (pinfunction "1_22") (pintype "passive"))
      (node (ref "X3") (pin "23") (pinfunction "1_23") (pintype "passive"))
      (node (ref "X3") (pin "24") (pinfunction "1_24") (pintype "passive"))
      (node (ref "X3") (pin "25") (pinfunction "1_25") (pintype "passive"))
      (node (ref "X3") (pin "26") (pinfunction "1_26") (pintype "passive"))
    )
    (net (code "72") (name "OUT-") (class "Default")
      (node (ref "R7") (pin "1") (pinfunction "1_1") (pintype "passive"))
      (node (ref "X3") (pin "17") (pinfunction "1_17") (pintype "passive"))
      (node (ref "X3") (pin "18") (pinfunction "1_18") (pintype "passive"))
      (node (ref "X3") (pin "19") (pinfunction "1_19") (pintype "passive"))
      (node (ref "X3") (pin "20") (pinfunction "1_20") (pintype "passive"))
      (node (ref "X3") (pin "21") (pinfunction "1_21") (pintype "passive"))
    )
    (net (code "73") (name "OUT_MON") (class "Default")
      (node (ref "JP1") (pin "2") (pinfunction "2_2") (pintype "passive"))
      (node (ref "MCU") (pin "A4") (pinfunction "ADC4_A4") (pintype "bidirectional"))
    )
    (net (code "74") (name "SCLK") (class "Default")
      (node (ref "MCU") (pin "ICSP_MISO") (pinfunction "MISO_ICSP_MISO") (pintype "bidirectional"))
      (node (ref "X3") (pin "9") (pinfunction "1_9") (pintype "passive"))
    )
    (net (code "75") (name "unconnected-(IC2-SYNC-Pad4)") (class "Default")
      (node (ref "IC2") (pin "4") (pinfunction "SYNC_4") (pintype "input"))
    )
    (net (code "76") (name "unconnected-(K1A-S-Pad12A)") (class "Default")
      (node (ref "K1") (pin "12A") (pinfunction "S_12A") (pintype "passive"))
    )
    (net (code "77") (name "unconnected-(K1B-S-Pad12B)") (class "Default")
      (node (ref "K1") (pin "12B") (pinfunction "S_12B") (pintype "passive"))
    )
    (net (code "78") (name "unconnected-(K_DC-PadO)") (class "Default")
      (node (ref "K_DC") (pin "O") (pinfunction "O_O") (pintype "passive"))
    )
    (net (code "79") (name "unconnected-(K_LOAD-PadO)") (class "Default")
      (node (ref "K_LOAD") (pin "O") (pinfunction "O_O") (pintype "passive"))
    )
    (net (code "80") (name "unconnected-(MCU-PadAREF)") (class "Default")
      (node (ref "MCU") (pin "AREF") (pinfunction "AREF_AREF") (pintype "bidirectional"))
    )
    (net (code "81") (name "unconnected-(MCU-PadGND)") (class "Default")
      (node (ref "MCU") (pin "GND") (pinfunction "GND_GND") (pintype "bidirectional"))
    )
    (net (code "82") (name "unconnected-(MCU-PadIOREF)") (class "Default")
      (node (ref "MCU") (pin "IOREF") (pinfunction "IOREF_IOREF") (pintype "bidirectional"))
    )
    (net (code "83") (name "unconnected-(MCU-PadN{slash}C)") (class "Default")
      (node (ref "MCU") (pin "N/C") (pinfunction "N/C_N/C") (pintype "no_connect"))
    )
    (net (code "84") (name "unconnected-(MCU-PadVIN)") (class "Default")
      (node (ref "MCU") (pin "VIN") (pinfunction "VIN_VIN") (pintype "bidirectional"))
    )
    (net (code "85") (name "unconnected-(MCUC-0(PE0)-Pad0)") (class "Default")
      (node (ref "MCU") (pin "0") (pinfunction "0(PE0)_0") (pintype "bidirectional"))
    )
    (net (code "86") (name "unconnected-(MCUD-+5V-PadICSP_+5V)") (class "Default")
      (node (ref "MCU") (pin "ICSP_+5V") (pinfunction "+5V_ICSP_+5V") (pintype "bidirectional"))
    )
    (net (code "87") (name "unconnected-(MCUD-~{RESET}-PadICSP_RESET)") (class "Default")
      (node (ref "MCU") (pin "ICSP_RESET") (pinfunction "~{RESET}_ICSP_RESET") (pintype "bidirectional"))
    )
    (net (code "88") (name "unconnected-(MCUE-~{RESET}-PadRESET)") (class "Default")
      (node (ref "MCU") (pin "RESET") (pinfunction "~{RESET}_RESET") (pintype "bidirectional"))
    )
    (net (code "89") (name "~{INT}") (class "Default")
      (node (ref "MCU") (pin "2") (pinfunction "2(PE4)_2") (pintype "bidirectional"))
      (node (ref "X3") (pin "8") (pinfunction "1_8") (pintype "passive"))
    )
    (net (code "90") (name "~{RESET_OUT}") (class "Default")
      (node (ref "MCU") (pin "3") (pinfunction "3(PE5)_3") (pintype "bidirectional"))
      (node (ref "X3") (pin "3") (pinfunction "1_3") (pintype "passive"))
    )
  )
)
